# VisualightMicroDIY_036_AA_gnd.net
KiCad netlist of a schematic drawn in EAGLE
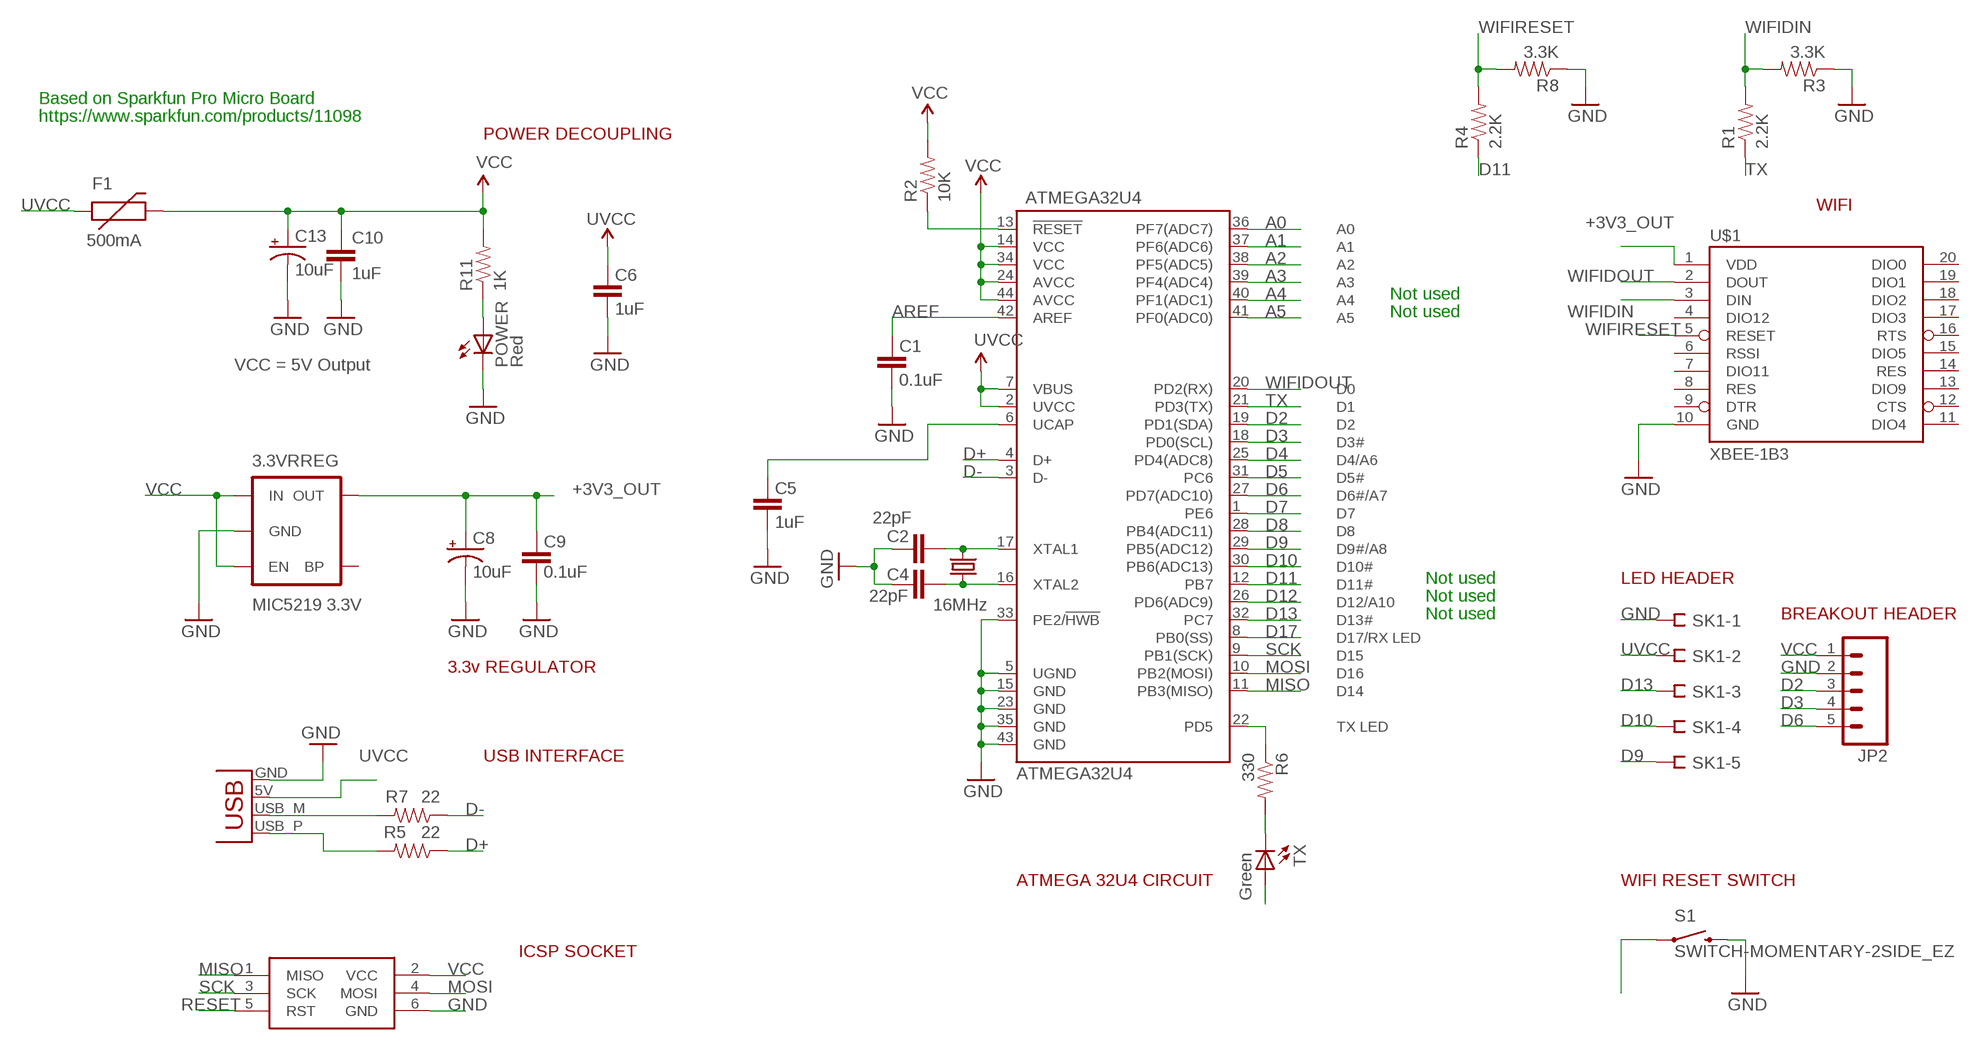
[diagram p0: schematic, sheet 1]

(export (version "E")
  (design (tool "Eeschema 10.0.6"))
  (components
    (comp (ref "3.3VRREG")
      (value "MIC5219 3.3V")
      (footprint "eagle-import:SOT23-5")
      (libsource (lib "eagle-import") (part "V_REG_MIC52193.3V"))
    )
    (comp (ref "ATMEGA32U4")
      (value "ATMEGA32U4")
      (footprint "eagle-import:SPARKFUN-DIGITALIC_QFN-44-NOPAD")
      (libsource (lib "eagle-import") (part "ATMEGA32U4QFN2"))
    )
    (comp (ref "C1")
      (value "0.1uF")
      (footprint "eagle-import:0402-CAP")
      (libsource (lib "eagle-import") (part "CAP0402-CAP"))
    )
    (comp (ref "C2")
      (value "22pF")
      (footprint "eagle-import:0402-CAP")
      (libsource (lib "eagle-import") (part "CAP0402-CAP"))
    )
    (comp (ref "C4")
      (value "22pF")
      (footprint "eagle-import:0402-CAP")
      (libsource (lib "eagle-import") (part "CAP0402-CAP"))
    )
    (comp (ref "C5")
      (value "1uF")
      (footprint "eagle-import:0402-CAP")
      (libsource (lib "eagle-import") (part "CAP0402-CAP"))
    )
    (comp (ref "C6")
      (value "1uF")
      (footprint "eagle-import:0402-CAP")
      (libsource (lib "eagle-import") (part "CAP0402-CAP"))
    )
    (comp (ref "C8")
      (value "10uF")
      (footprint "eagle-import:EIA3216")
      (libsource (lib "eagle-import") (part "CAP_POL1206"))
    )
    (comp (ref "C9")
      (value "0.1uF")
      (footprint "eagle-import:0402-CAP")
      (libsource (lib "eagle-import") (part "CAP0402-CAP"))
    )
    (comp (ref "C10")
      (value "1uF")
      (footprint "eagle-import:0402-CAP")
      (libsource (lib "eagle-import") (part "CAP0402-CAP"))
    )
    (comp (ref "C13")
      (value "10uF")
      (footprint "eagle-import:EIA3216")
      (libsource (lib "eagle-import") (part "CAP_POL1206"))
    )
    (comp (ref "F1")
      (value "500mA")
      (footprint "eagle-import:PTC-1206")
      (libsource (lib "eagle-import") (part "PTCSMD"))
    )
    (comp (ref "ISP1")
      (value "AVRISP-6")
      (footprint "eagle-import:AVRISP")
      (libsource (lib "eagle-import") (part "AVRISP-6"))
    )
    (comp (ref "JP2")
      (value "M05PTH")
      (footprint "eagle-import:1X05")
      (libsource (lib "eagle-import") (part "M05PTH"))
    )
    (comp (ref "POWER")
      (value "Red")
      (footprint "eagle-import:LED-0603")
      (libsource (lib "eagle-import") (part "LED0603"))
    )
    (comp (ref "R1")
      (value "2.2K")
      (footprint "eagle-import:0402-RES")
      (libsource (lib "eagle-import") (part "RESISTOR0402-RES"))
    )
    (comp (ref "R2")
      (value "10K")
      (footprint "eagle-import:0402-RES")
      (libsource (lib "eagle-import") (part "RESISTOR0402-RES"))
    )
    (comp (ref "R3")
      (value "3.3K")
      (footprint "eagle-import:0402-RES")
      (libsource (lib "eagle-import") (part "RESISTOR0402-RES"))
    )
    (comp (ref "R4")
      (value "2.2K")
      (footprint "eagle-import:0402-RES")
      (libsource (lib "eagle-import") (part "RESISTOR0402-RES"))
    )
    (comp (ref "R5")
      (value "22")
      (footprint "eagle-import:0402-RES")
      (libsource (lib "eagle-import") (part "RESISTOR0402-RES"))
    )
    (comp (ref "R6")
      (value "330")
      (footprint "eagle-import:0402-RES")
      (libsource (lib "eagle-import") (part "RESISTOR0402-RES"))
    )
    (comp (ref "R7")
      (value "22")
      (footprint "eagle-import:0402-RES")
      (libsource (lib "eagle-import") (part "RESISTOR0402-RES"))
    )
    (comp (ref "R8")
      (value "3.3K")
      (footprint "eagle-import:0402-RES")
      (libsource (lib "eagle-import") (part "RESISTOR0402-RES"))
    )
    (comp (ref "R11")
      (value "1K")
      (footprint "eagle-import:0402-RES")
      (libsource (lib "eagle-import") (part "RESISTOR0402-RES"))
    )
    (comp (ref "S1")
      (value "SWITCH-MOMENTARY-2SIDE_EZ")
      (footprint "eagle-import:TACTILE-PTH-SIDEEZ")
      (libsource (lib "eagle-import") (part "SWITCH-MOMENTARY-2SIDE_EZ"))
    )
    (comp (ref "SK1")
      (value "DF3-05S")
      (footprint "eagle-import:DF3S-05")
      (libsource (lib "eagle-import") (part "DF3-05S"))
    )
    (comp (ref "TX")
      (value "Green")
      (footprint "eagle-import:LED-0603")
      (libsource (lib "eagle-import") (part "LED0603"))
    )
    (comp (ref "U$1")
      (value "XBEE-1B3")
      (footprint "eagle-import:XBEE-SMD")
      (libsource (lib "eagle-import") (part "XBEE-1B3"))
    )
    (comp (ref "X2")
      (value "USBPCB")
      (footprint "eagle-import:USB-A-PCB")
      (libsource (lib "eagle-import") (part "USBPCB"))
    )
    (comp (ref "Y1")
      (value "16MHz")
      (footprint "eagle-import:CRYSTAL-SMD-5X3")
      (libsource (lib "eagle-import") (part "CRYSTAL5X3"))
    )
  )
  (nets
    (net (code "1") (name "/+3V3_OUT") (class "Default")
      (node (ref "3.3VRREG") (pin "5") (pinfunction "OUT_5") (pintype "passive"))
      (node (ref "C8") (pin "A") (pinfunction "+_A") (pintype "passive"))
      (node (ref "C9") (pin "2") (pinfunction "2_2") (pintype "passive"))
      (node (ref "U$1") (pin "1") (pinfunction "VDD_1") (pintype "power_in"))
    )
    (net (code "2") (name "/A0") (class "Default")
      (node (ref "ATMEGA32U4") (pin "36") (pinfunction "PF7(ADC7)_36") (pintype "bidirectional"))
    )
    (net (code "3") (name "/A1") (class "Default")
      (node (ref "ATMEGA32U4") (pin "37") (pinfunction "PF6(ADC6)_37") (pintype "bidirectional"))
    )
    (net (code "4") (name "/A2") (class "Default")
      (node (ref "ATMEGA32U4") (pin "38") (pinfunction "PF5(ADC5)_38") (pintype "bidirectional"))
    )
    (net (code "5") (name "/A3") (class "Default")
      (node (ref "ATMEGA32U4") (pin "39") (pinfunction "PF4(ADC4)_39") (pintype "bidirectional"))
    )
    (net (code "6") (name "/A4") (class "Default")
      (node (ref "ATMEGA32U4") (pin "40") (pinfunction "PF1(ADC1)_40") (pintype "bidirectional"))
    )
    (net (code "7") (name "/A5") (class "Default")
      (node (ref "ATMEGA32U4") (pin "41") (pinfunction "PF0(ADC0)_41") (pintype "bidirectional"))
    )
    (net (code "8") (name "/AREF") (class "Default")
      (node (ref "ATMEGA32U4") (pin "42") (pinfunction "AREF_42") (pintype "bidirectional"))
      (node (ref "C1") (pin "2") (pinfunction "2_2") (pintype "passive"))
    )
    (net (code "9") (name "/D+") (class "Default")
      (node (ref "ATMEGA32U4") (pin "4") (pinfunction "D+_4") (pintype "bidirectional"))
      (node (ref "R5") (pin "1") (pinfunction "1_1") (pintype "passive"))
    )
    (net (code "10") (name "/D-") (class "Default")
      (node (ref "ATMEGA32U4") (pin "3") (pinfunction "D-_3") (pintype "bidirectional"))
      (node (ref "R7") (pin "1") (pinfunction "1_1") (pintype "passive"))
    )
    (net (code "11") (name "/D2") (class "Default")
      (node (ref "ATMEGA32U4") (pin "19") (pinfunction "PD1(SDA)_19") (pintype "bidirectional"))
      (node (ref "JP2") (pin "3") (pinfunction "3_3") (pintype "passive"))
    )
    (net (code "12") (name "/D3") (class "Default")
      (node (ref "ATMEGA32U4") (pin "18") (pinfunction "PD0(SCL)_18") (pintype "bidirectional"))
      (node (ref "JP2") (pin "4") (pinfunction "4_4") (pintype "passive"))
    )
    (net (code "13") (name "/D4") (class "Default")
      (node (ref "ATMEGA32U4") (pin "25") (pinfunction "PD4(ADC8)_25") (pintype "bidirectional"))
    )
    (net (code "14") (name "/D5") (class "Default")
      (node (ref "ATMEGA32U4") (pin "31") (pinfunction "PC6_31") (pintype "bidirectional"))
    )
    (net (code "15") (name "/D6") (class "Default")
      (node (ref "ATMEGA32U4") (pin "27") (pinfunction "PD7(ADC10)_27") (pintype "bidirectional"))
      (node (ref "JP2") (pin "5") (pinfunction "5_5") (pintype "passive"))
    )
    (net (code "16") (name "/D7") (class "Default")
      (node (ref "ATMEGA32U4") (pin "1") (pinfunction "PE6_1") (pintype "bidirectional"))
      (node (ref "S1") (pin "1") (pinfunction "1_1") (pintype "passive"))
    )
    (net (code "17") (name "/D8") (class "Default")
      (node (ref "ATMEGA32U4") (pin "28") (pinfunction "PB4(ADC11)_28") (pintype "bidirectional"))
    )
    (net (code "18") (name "/D9") (class "Default")
      (node (ref "ATMEGA32U4") (pin "29") (pinfunction "PB5(ADC12)_29") (pintype "bidirectional"))
      (node (ref "SK1") (pin "5") (pinfunction "S_5") (pintype "passive"))
    )
    (net (code "19") (name "/D10") (class "Default")
      (node (ref "ATMEGA32U4") (pin "30") (pinfunction "PB6(ADC13)_30") (pintype "bidirectional"))
      (node (ref "SK1") (pin "4") (pinfunction "S_4") (pintype "passive"))
    )
    (net (code "20") (name "/D11") (class "Default")
      (node (ref "ATMEGA32U4") (pin "12") (pinfunction "PB7_12") (pintype "bidirectional"))
      (node (ref "R4") (pin "1") (pinfunction "1_1") (pintype "passive"))
    )
    (net (code "21") (name "/D12") (class "Default")
      (node (ref "ATMEGA32U4") (pin "26") (pinfunction "PD6(ADC9)_26") (pintype "bidirectional"))
    )
    (net (code "22") (name "/D13") (class "Default")
      (node (ref "ATMEGA32U4") (pin "32") (pinfunction "PC7_32") (pintype "bidirectional"))
      (node (ref "SK1") (pin "3") (pinfunction "S_3") (pintype "passive"))
    )
    (net (code "23") (name "/D17") (class "Default")
      (node (ref "ATMEGA32U4") (pin "8") (pinfunction "PB0(SS)_8") (pintype "bidirectional"))
    )
    (net (code "24") (name "/MISO") (class "Default")
      (node (ref "ATMEGA32U4") (pin "11") (pinfunction "PB3(MISO)_11") (pintype "bidirectional"))
      (node (ref "ISP1") (pin "1") (pinfunction "MISO_1") (pintype "input"))
    )
    (net (code "25") (name "/MOSI") (class "Default")
      (node (ref "ATMEGA32U4") (pin "10") (pinfunction "PB2(MOSI)_10") (pintype "bidirectional"))
      (node (ref "ISP1") (pin "4") (pinfunction "MOSI_4") (pintype "output"))
    )
    (net (code "26") (name "/RESET") (class "Default")
      (node (ref "ATMEGA32U4") (pin "13") (pinfunction "~{RESET}_13") (pintype "bidirectional"))
      (node (ref "ISP1") (pin "5") (pinfunction "RST_5") (pintype "output"))
      (node (ref "R2") (pin "1") (pinfunction "1_1") (pintype "passive"))
    )
    (net (code "27") (name "/SCK") (class "Default")
      (node (ref "ATMEGA32U4") (pin "9") (pinfunction "PB1(SCK)_9") (pintype "bidirectional"))
      (node (ref "ISP1") (pin "3") (pinfunction "SCK_3") (pintype "output"))
    )
    (net (code "28") (name "/TX") (class "Default")
      (node (ref "ATMEGA32U4") (pin "21") (pinfunction "PD3(TX)_21") (pintype "bidirectional"))
      (node (ref "R1") (pin "1") (pinfunction "1_1") (pintype "passive"))
    )
    (net (code "29") (name "/WIFIDIN") (class "Default")
      (node (ref "R1") (pin "2") (pinfunction "2_2") (pintype "passive"))
      (node (ref "R3") (pin "2") (pinfunction "2_2") (pintype "passive"))
      (node (ref "U$1") (pin "3") (pinfunction "DIN_3") (pintype "input"))
    )
    (net (code "30") (name "/WIFIDOUT") (class "Default")
      (node (ref "ATMEGA32U4") (pin "20") (pinfunction "PD2(RX)_20") (pintype "bidirectional"))
      (node (ref "U$1") (pin "2") (pinfunction "DOUT_2") (pintype "output"))
    )
    (net (code "31") (name "/WIFIRESET") (class "Default")
      (node (ref "R4") (pin "2") (pinfunction "2_2") (pintype "passive"))
      (node (ref "R8") (pin "2") (pinfunction "2_2") (pintype "passive"))
      (node (ref "U$1") (pin "5") (pinfunction "RESET_5") (pintype "input"))
    )
    (net (code "32") (name "GND") (class "Default")
      (node (ref "3.3VRREG") (pin "2") (pinfunction "GND_2") (pintype "input"))
      (node (ref "ATMEGA32U4") (pin "15") (pinfunction "GND_15") (pintype "bidirectional"))
      (node (ref "ATMEGA32U4") (pin "23") (pinfunction "GND_23") (pintype "bidirectional"))
      (node (ref "ATMEGA32U4") (pin "33") (pinfunction "PE2/~{HWB}_33") (pintype "bidirectional"))
      (node (ref "ATMEGA32U4") (pin "35") (pinfunction "GND_35") (pintype "bidirectional"))
      (node (ref "ATMEGA32U4") (pin "43") (pinfunction "GND_43") (pintype "bidirectional"))
      (node (ref "ATMEGA32U4") (pin "5") (pinfunction "UGND_5") (pintype "bidirectional"))
      (node (ref "C1") (pin "1") (pinfunction "1_1") (pintype "passive"))
      (node (ref "C10") (pin "2") (pinfunction "2_2") (pintype "passive"))
      (node (ref "C13") (pin "C") (pinfunction "-_C") (pintype "passive"))
      (node (ref "C2") (pin "2") (pinfunction "2_2") (pintype "passive"))
      (node (ref "C4") (pin "2") (pinfunction "2_2") (pintype "passive"))
      (node (ref "C5") (pin "1") (pinfunction "1_1") (pintype "passive"))
      (node (ref "C6") (pin "1") (pinfunction "1_1") (pintype "passive"))
      (node (ref "C8") (pin "C") (pinfunction "-_C") (pintype "passive"))
      (node (ref "C9") (pin "1") (pinfunction "1_1") (pintype "passive"))
      (node (ref "ISP1") (pin "6") (pinfunction "GND_6") (pintype "power_in"))
      (node (ref "JP2") (pin "2") (pinfunction "2_2") (pintype "passive"))
      (node (ref "POWER") (pin "C") (pinfunction "C_C") (pintype "passive"))
      (node (ref "R3") (pin "1") (pinfunction "1_1") (pintype "passive"))
      (node (ref "R8") (pin "1") (pinfunction "1_1") (pintype "passive"))
      (node (ref "S1") (pin "2") (pinfunction "2_2") (pintype "passive"))
      (node (ref "SK1") (pin "1") (pinfunction "S_1") (pintype "passive"))
      (node (ref "U$1") (pin "10") (pinfunction "GND_10") (pintype "power_in"))
      (node (ref "X2") (pin "GND") (pinfunction "GND_GND") (pintype "bidirectional"))
    )
    (net (code "33") (name "Net-(ATMEGA32U4-PD5)") (class "Default")
      (node (ref "ATMEGA32U4") (pin "22") (pinfunction "PD5_22") (pintype "bidirectional"))
      (node (ref "R6") (pin "1") (pinfunction "1_1") (pintype "passive"))
    )
    (net (code "34") (name "Net-(ATMEGA32U4-UCAP)") (class "Default")
      (node (ref "ATMEGA32U4") (pin "6") (pinfunction "UCAP_6") (pintype "bidirectional"))
      (node (ref "C5") (pin "2") (pinfunction "2_2") (pintype "passive"))
    )
    (net (code "35") (name "Net-(ATMEGA32U4-XTAL1)") (class "Default")
      (node (ref "ATMEGA32U4") (pin "17") (pinfunction "XTAL1_17") (pintype "bidirectional"))
      (node (ref "C2") (pin "1") (pinfunction "1_1") (pintype "passive"))
      (node (ref "Y1") (pin "3") (pinfunction "2_3") (pintype "passive"))
    )
    (net (code "36") (name "Net-(ATMEGA32U4-XTAL2)") (class "Default")
      (node (ref "ATMEGA32U4") (pin "16") (pinfunction "XTAL2_16") (pintype "bidirectional"))
      (node (ref "C4") (pin "1") (pinfunction "1_1") (pintype "passive"))
      (node (ref "Y1") (pin "1") (pinfunction "1_1") (pintype "passive"))
    )
    (net (code "37") (name "Net-(POWER-PadA)") (class "Default")
      (node (ref "POWER") (pin "A") (pinfunction "A_A") (pintype "passive"))
      (node (ref "R11") (pin "1") (pinfunction "1_1") (pintype "passive"))
    )
    (net (code "38") (name "Net-(R6-Pad2)") (class "Default")
      (node (ref "R6") (pin "2") (pinfunction "2_2") (pintype "passive"))
      (node (ref "TX") (pin "C") (pinfunction "C_C") (pintype "passive"))
    )
    (net (code "39") (name "Net-(X2-D+)") (class "Default")
      (node (ref "R5") (pin "2") (pinfunction "2_2") (pintype "passive"))
      (node (ref "X2") (pin "USB_P") (pinfunction "D+_USB_P") (pintype "bidirectional"))
    )
    (net (code "40") (name "Net-(X2-D-)") (class "Default")
      (node (ref "R7") (pin "2") (pinfunction "2_2") (pintype "passive"))
      (node (ref "X2") (pin "USB_M") (pinfunction "D-_USB_M") (pintype "bidirectional"))
    )
    (net (code "41") (name "UVCC") (class "Default")
      (node (ref "ATMEGA32U4") (pin "2") (pinfunction "UVCC_2") (pintype "bidirectional"))
      (node (ref "ATMEGA32U4") (pin "7") (pinfunction "VBUS_7") (pintype "bidirectional"))
      (node (ref "C6") (pin "2") (pinfunction "2_2") (pintype "passive"))
      (node (ref "F1") (pin "1") (pinfunction "1_1") (pintype "bidirectional"))
      (node (ref "SK1") (pin "2") (pinfunction "S_2") (pintype "passive"))
      (node (ref "X2") (pin "5V") (pinfunction "VBUS_5V") (pintype "bidirectional"))
    )
    (net (code "42") (name "VCC") (class "Default")
      (node (ref "3.3VRREG") (pin "1") (pinfunction "IN_1") (pintype "input"))
      (node (ref "3.3VRREG") (pin "3") (pinfunction "EN_3") (pintype "input"))
      (node (ref "ATMEGA32U4") (pin "14") (pinfunction "VCC_14") (pintype "bidirectional"))
      (node (ref "ATMEGA32U4") (pin "24") (pinfunction "AVCC_24") (pintype "bidirectional"))
      (node (ref "ATMEGA32U4") (pin "34") (pinfunction "VCC_34") (pintype "bidirectional"))
      (node (ref "ATMEGA32U4") (pin "44") (pinfunction "AVCC_44") (pintype "bidirectional"))
      (node (ref "C10") (pin "1") (pinfunction "1_1") (pintype "passive"))
      (node (ref "C13") (pin "A") (pinfunction "+_A") (pintype "passive"))
      (node (ref "F1") (pin "2") (pinfunction "2_2") (pintype "bidirectional"))
      (node (ref "ISP1") (pin "2") (pinfunction "VCC_2") (pintype "power_in"))
      (node (ref "JP2") (pin "1") (pinfunction "1_1") (pintype "passive"))
      (node (ref "R11") (pin "2") (pinfunction "2_2") (pintype "passive"))
      (node (ref "R2") (pin "2") (pinfunction "2_2") (pintype "passive"))
      (node (ref "TX") (pin "A") (pinfunction "A_A") (pintype "passive"))
    )
    (net (code "43") (name "unconnected-(3.3VRREG-BP-Pad4)") (class "Default")
      (node (ref "3.3VRREG") (pin "4") (pinfunction "BP_4") (pintype "input"))
    )
    (net (code "44") (name "unconnected-(U$1-CTS-Pad12)") (class "Default")
      (node (ref "U$1") (pin "12") (pinfunction "CTS_12") (pintype "output"))
    )
    (net (code "45") (name "unconnected-(U$1-DIO0-Pad20)") (class "Default")
      (node (ref "U$1") (pin "20") (pinfunction "DIO0_20") (pintype "bidirectional"))
    )
    (net (code "46") (name "unconnected-(U$1-DIO1-Pad19)") (class "Default")
      (node (ref "U$1") (pin "19") (pinfunction "DIO1_19") (pintype "bidirectional"))
    )
    (net (code "47") (name "unconnected-(U$1-DIO2-Pad18)") (class "Default")
      (node (ref "U$1") (pin "18") (pinfunction "DIO2_18") (pintype "bidirectional"))
    )
    (net (code "48") (name "unconnected-(U$1-DIO3-Pad17)") (class "Default")
      (node (ref "U$1") (pin "17") (pinfunction "DIO3_17") (pintype "bidirectional"))
    )
    (net (code "49") (name "unconnected-(U$1-DIO4-Pad11)") (class "Default")
      (node (ref "U$1") (pin "11") (pinfunction "DIO4_11") (pintype "bidirectional"))
    )
    (net (code "50") (name "unconnected-(U$1-DIO5-Pad15)") (class "Default")
      (node (ref "U$1") (pin "15") (pinfunction "DIO5_15") (pintype "bidirectional"))
    )
    (net (code "51") (name "unconnected-(U$1-DIO9-Pad13)") (class "Default")
      (node (ref "U$1") (pin "13") (pinfunction "DIO9_13") (pintype "bidirectional"))
    )
    (net (code "52") (name "unconnected-(U$1-DIO11-Pad7)") (class "Default")
      (node (ref "U$1") (pin "7") (pinfunction "DIO11_7") (pintype "bidirectional"))
    )
    (net (code "53") (name "unconnected-(U$1-DIO12-Pad4)") (class "Default")
      (node (ref "U$1") (pin "4") (pinfunction "DIO12_4") (pintype "bidirectional"))
    )
    (net (code "54") (name "unconnected-(U$1-DTR-Pad9)") (class "Default")
      (node (ref "U$1") (pin "9") (pinfunction "DTR_9") (pintype "bidirectional"))
    )
    (net (code "55") (name "unconnected-(U$1-RES-Pad8)") (class "Default")
      (node (ref "U$1") (pin "8") (pinfunction "RES_8") (pintype "bidirectional"))
    )
    (net (code "56") (name "unconnected-(U$1-RES-Pad14)") (class "Default")
      (node (ref "U$1") (pin "14") (pinfunction "RES_14") (pintype "bidirectional"))
    )
    (net (code "57") (name "unconnected-(U$1-RSSI-Pad6)") (class "Default")
      (node (ref "U$1") (pin "6") (pinfunction "RSSI_6") (pintype "bidirectional"))
    )
    (net (code "58") (name "unconnected-(U$1-RTS-Pad16)") (class "Default")
      (node (ref "U$1") (pin "16") (pinfunction "RTS_16") (pintype "input"))
    )
  )
)
